# openSX70-dongle_v6-1-dual-led.net
KiCad netlist of a schematic drawn in EAGLE
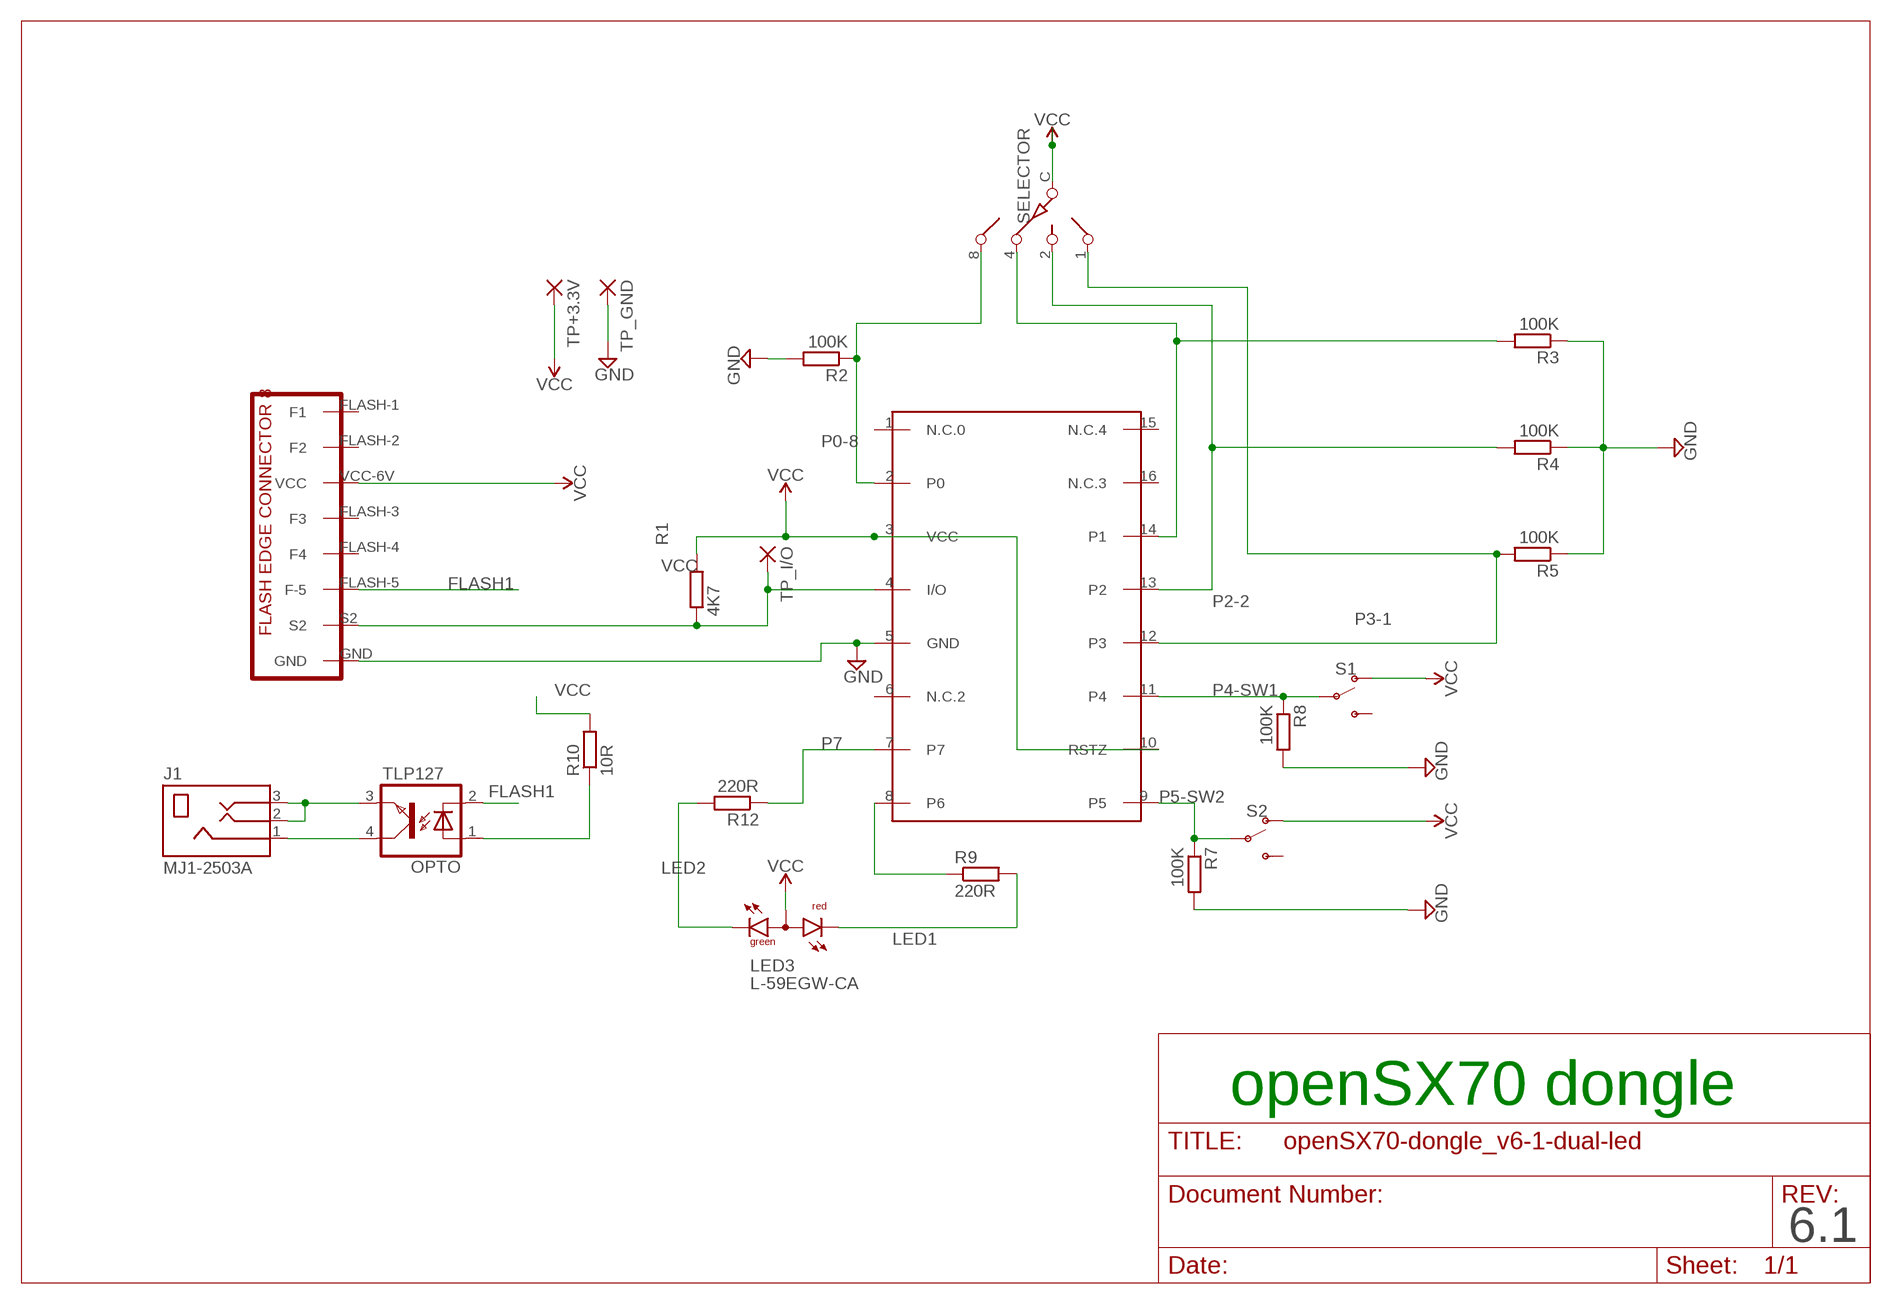
[diagram p0: schematic, sheet 1]

(export (version "E")
  (design (tool "Eeschema 10.0.6"))
  (components
    (comp (ref "DS2408")
      (value "DS2408")
      (footprint "eagle-import:SO16")
      (libsource (lib "eagle-import") (part "DS2408"))
    )
    (comp (ref "J1")
      (value "MJ1-2503A")
      (footprint "eagle-import:CUI_MJ1-2503A")
      (fields (field (name "DIGI-KEY_PART_NUMBER") "CP1-2503AM-ND") (field (name "MF") "CUI Inc."))
      (libsource (lib "eagle-import") (part "MJ1-2503A"))
    )
    (comp (ref "LED3")
      (value "L-59EGW-CA")
      (footprint "eagle-import:L-59EGW-CA")
      (libsource (lib "eagle-import") (part "L-59EGW-CA"))
    )
    (comp (ref "OPTO")
      (value "TLP127")
      (footprint "eagle-import:SO-4")
      (libsource (lib "eagle-import") (part "TLP127"))
    )
    (comp (ref "R1")
      (value "4K7")
      (footprint "eagle-import:R0603")
      (libsource (lib "eagle-import") (part "R-EU_R0603"))
    )
    (comp (ref "R2")
      (value "100K")
      (footprint "eagle-import:R0603")
      (libsource (lib "eagle-import") (part "R-EU_R0603"))
    )
    (comp (ref "R3")
      (value "100K")
      (footprint "eagle-import:R0603")
      (libsource (lib "eagle-import") (part "R-EU_R0603"))
    )
    (comp (ref "R4")
      (value "100K")
      (footprint "eagle-import:R0603")
      (libsource (lib "eagle-import") (part "R-EU_R0603"))
    )
    (comp (ref "R5")
      (value "100K")
      (footprint "eagle-import:R0603")
      (libsource (lib "eagle-import") (part "R-EU_R0603"))
    )
    (comp (ref "R7")
      (value "100K")
      (footprint "eagle-import:R0603")
      (libsource (lib "eagle-import") (part "R-EU_R0603"))
    )
    (comp (ref "R8")
      (value "100K")
      (footprint "eagle-import:R0603")
      (libsource (lib "eagle-import") (part "R-EU_R0603"))
    )
    (comp (ref "R9")
      (value "220R")
      (footprint "eagle-import:R0603")
      (libsource (lib "eagle-import") (part "R-EU_R0603"))
    )
    (comp (ref "R10")
      (value "10R")
      (footprint "eagle-import:R0603")
      (libsource (lib "eagle-import") (part "resistor_348_R-EU_R0603"))
    )
    (comp (ref "R12")
      (value "220R")
      (footprint "eagle-import:R0603")
      (libsource (lib "eagle-import") (part "R-EU_R0603"))
    )
    (comp (ref "S1")
      (value "SWITCH-SPDT-SMD-RIGHT-ANGLE")
      (footprint "eagle-import:SWITCH_SPST_SMD_A")
      (libsource (lib "eagle-import") (part "SWITCH-SPDT-SMD-RIGHT-ANGLE"))
    )
    (comp (ref "S2")
      (value "SWITCH-SPDT-SMD-RIGHT-ANGLE")
      (footprint "eagle-import:SWITCH_SPST_SMD_A")
      (libsource (lib "eagle-import") (part "SWITCH-SPDT-SMD-RIGHT-ANGLE"))
    )
    (comp (ref "SELECTOR")
      (value "SW-C16")
      (footprint "eagle-import:SW-C16")
      (libsource (lib "eagle-import") (part "SW-C16"))
    )
    (comp (ref "TP+3.3V")
      (value "SMD2")
      (footprint "eagle-import:SMD1,27-2,54")
      (libsource (lib "eagle-import") (part "SMD2"))
    )
    (comp (ref "TP_GND")
      (value "SMD2")
      (footprint "eagle-import:SMD1,27-2,54")
      (libsource (lib "eagle-import") (part "SMD2"))
    )
    (comp (ref "TP_I/O")
      (value "SMD2")
      (footprint "eagle-import:SMD1,27-2,54")
      (libsource (lib "eagle-import") (part "SMD2"))
    )
    (comp (ref "U$2")
      (value "SX70-FLASH-EDGE8-MALE-PROPER")
      (footprint "eagle-import:SX70-FLASH-EDGE8")
      (libsource (lib "eagle-import") (part "SX70-FLASH-EDGE8-MALE-PROPER"))
    )
  )
  (nets
    (net (code "1") (name "/FLASH1") (class "Default")
      (node (ref "OPTO") (pin "2") (pinfunction "C_2") (pintype "passive"))
      (node (ref "U$2") (pin "FLASH-5") (pinfunction "F-5_FLASH-5") (pintype "bidirectional"))
    )
    (net (code "2") (name "/LED1") (class "Default")
      (node (ref "LED3") (pin "1") (pinfunction "CR_1") (pintype "passive"))
      (node (ref "R9") (pin "2") (pinfunction "2_2") (pintype "passive"))
    )
    (net (code "3") (name "/LED2") (class "Default")
      (node (ref "LED3") (pin "3") (pinfunction "CG_3") (pintype "passive"))
      (node (ref "R12") (pin "2") (pinfunction "2_2") (pintype "passive"))
    )
    (net (code "4") (name "/P0-8") (class "Default")
      (node (ref "DS2408") (pin "2") (pinfunction "P0_2") (pintype "bidirectional"))
      (node (ref "R2") (pin "1") (pinfunction "1_1") (pintype "passive"))
      (node (ref "SELECTOR") (pin "8") (pinfunction "8_8") (pintype "passive"))
    )
    (net (code "5") (name "/P2-2") (class "Default")
      (node (ref "DS2408") (pin "13") (pinfunction "P2_13") (pintype "bidirectional"))
      (node (ref "R4") (pin "2") (pinfunction "2_2") (pintype "passive"))
      (node (ref "SELECTOR") (pin "2") (pinfunction "2_2") (pintype "passive"))
    )
    (net (code "6") (name "/P3-1") (class "Default")
      (node (ref "DS2408") (pin "12") (pinfunction "P3_12") (pintype "bidirectional"))
      (node (ref "R5") (pin "2") (pinfunction "2_2") (pintype "passive"))
      (node (ref "SELECTOR") (pin "1") (pinfunction "1_1") (pintype "passive"))
    )
    (net (code "7") (name "/P4-SW1") (class "Default")
      (node (ref "DS2408") (pin "11") (pinfunction "P4_11") (pintype "bidirectional"))
      (node (ref "R8") (pin "1") (pinfunction "1_1") (pintype "passive"))
      (node (ref "S1") (pin "2") (pinfunction "P_2") (pintype "passive"))
    )
    (net (code "8") (name "/P5-SW2") (class "Default")
      (node (ref "DS2408") (pin "9") (pinfunction "P5_9") (pintype "bidirectional"))
      (node (ref "R7") (pin "1") (pinfunction "1_1") (pintype "passive"))
      (node (ref "S2") (pin "2") (pinfunction "P_2") (pintype "passive"))
    )
    (net (code "9") (name "/P7") (class "Default")
      (node (ref "DS2408") (pin "7") (pinfunction "P7_7") (pintype "bidirectional"))
      (node (ref "R12") (pin "1") (pinfunction "1_1") (pintype "passive"))
    )
    (net (code "10") (name "GND") (class "Default")
      (node (ref "DS2408") (pin "5") (pinfunction "GND_5") (pintype "bidirectional"))
      (node (ref "R2") (pin "2") (pinfunction "2_2") (pintype "passive"))
      (node (ref "R3") (pin "1") (pinfunction "1_1") (pintype "passive"))
      (node (ref "R4") (pin "1") (pinfunction "1_1") (pintype "passive"))
      (node (ref "R5") (pin "1") (pinfunction "1_1") (pintype "passive"))
      (node (ref "R7") (pin "2") (pinfunction "2_2") (pintype "passive"))
      (node (ref "R8") (pin "2") (pinfunction "2_2") (pintype "passive"))
      (node (ref "TP_GND") (pin "1") (pinfunction "P_1") (pintype "passive"))
      (node (ref "U$2") (pin "GND") (pinfunction "GND_GND") (pintype "bidirectional"))
    )
    (net (code "11") (name "Net-(DS2408-I{slash}O)") (class "Default")
      (node (ref "DS2408") (pin "4") (pinfunction "I/O_4") (pintype "bidirectional"))
      (node (ref "R1") (pin "1") (pinfunction "1_1") (pintype "passive"))
      (node (ref "TP_I/O") (pin "1") (pinfunction "P_1") (pintype "passive"))
      (node (ref "U$2") (pin "S2") (pinfunction "S2_S2") (pintype "bidirectional"))
    )
    (net (code "12") (name "Net-(DS2408-P1)") (class "Default")
      (node (ref "DS2408") (pin "14") (pinfunction "P1_14") (pintype "bidirectional"))
      (node (ref "R3") (pin "2") (pinfunction "2_2") (pintype "passive"))
      (node (ref "SELECTOR") (pin "4") (pinfunction "4_4") (pintype "passive"))
    )
    (net (code "13") (name "Net-(DS2408-P6)") (class "Default")
      (node (ref "DS2408") (pin "8") (pinfunction "P6_8") (pintype "bidirectional"))
      (node (ref "R9") (pin "1") (pinfunction "1_1") (pintype "passive"))
    )
    (net (code "14") (name "Net-(OPTO-A)") (class "Default")
      (node (ref "OPTO") (pin "1") (pinfunction "A_1") (pintype "passive"))
      (node (ref "R10") (pin "1") (pinfunction "1_1") (pintype "passive"))
    )
    (net (code "15") (name "Net-(OPTO-COL)") (class "Default")
      (node (ref "J1") (pin "1") (pinfunction "1_1") (pintype "passive"))
      (node (ref "OPTO") (pin "4") (pinfunction "COL_4") (pintype "passive"))
    )
    (net (code "16") (name "Net-(OPTO-EMIT)") (class "Default")
      (node (ref "J1") (pin "2") (pinfunction "2_2") (pintype "passive"))
      (node (ref "J1") (pin "3") (pinfunction "3_3") (pintype "passive"))
      (node (ref "OPTO") (pin "3") (pinfunction "EMIT_3") (pintype "passive"))
    )
    (net (code "17") (name "VCC") (class "Default")
      (node (ref "DS2408") (pin "10") (pinfunction "RSTZ_10") (pintype "bidirectional"))
      (node (ref "DS2408") (pin "3") (pinfunction "VCC_3") (pintype "bidirectional"))
      (node (ref "LED3") (pin "2") (pinfunction "A_2") (pintype "passive"))
      (node (ref "R1") (pin "2") (pinfunction "2_2") (pintype "passive"))
      (node (ref "R10") (pin "2") (pinfunction "2_2") (pintype "passive"))
      (node (ref "S1") (pin "1") (pinfunction "O_1") (pintype "passive"))
      (node (ref "S2") (pin "1") (pinfunction "O_1") (pintype "passive"))
      (node (ref "SELECTOR") (pin "C") (pinfunction "C_C") (pintype "passive"))
      (node (ref "TP+3.3V") (pin "1") (pinfunction "P_1") (pintype "passive"))
      (node (ref "U$2") (pin "VCC-6V") (pinfunction "VCC_VCC-6V") (pintype "bidirectional"))
    )
    (net (code "18") (name "unconnected-(DS2408-N.C.0-Pad1)") (class "Default")
      (node (ref "DS2408") (pin "1") (pinfunction "N.C.0_1") (pintype "bidirectional"))
    )
    (net (code "19") (name "unconnected-(DS2408-N.C.2-Pad6)") (class "Default")
      (node (ref "DS2408") (pin "6") (pinfunction "N.C.2_6") (pintype "bidirectional"))
    )
    (net (code "20") (name "unconnected-(DS2408-N.C.3-Pad16)") (class "Default")
      (node (ref "DS2408") (pin "16") (pinfunction "N.C.3_16") (pintype "bidirectional"))
    )
    (net (code "21") (name "unconnected-(DS2408-N.C.4-Pad15)") (class "Default")
      (node (ref "DS2408") (pin "15") (pinfunction "N.C.4_15") (pintype "bidirectional"))
    )
    (net (code "22") (name "unconnected-(S1-S-Pad3)") (class "Default")
      (node (ref "S1") (pin "3") (pinfunction "S_3") (pintype "passive"))
    )
    (net (code "23") (name "unconnected-(S2-S-Pad3)") (class "Default")
      (node (ref "S2") (pin "3") (pinfunction "S_3") (pintype "passive"))
    )
    (net (code "24") (name "unconnected-(U$2-F1-PadFLASH-1)") (class "Default")
      (node (ref "U$2") (pin "FLASH-1") (pinfunction "F1_FLASH-1") (pintype "bidirectional"))
    )
    (net (code "25") (name "unconnected-(U$2-F2-PadFLASH-2)") (class "Default")
      (node (ref "U$2") (pin "FLASH-2") (pinfunction "F2_FLASH-2") (pintype "bidirectional"))
    )
    (net (code "26") (name "unconnected-(U$2-F3-PadFLASH-3)") (class "Default")
      (node (ref "U$2") (pin "FLASH-3") (pinfunction "F3_FLASH-3") (pintype "bidirectional"))
    )
    (net (code "27") (name "unconnected-(U$2-F4-PadFLASH-4)") (class "Default")
      (node (ref "U$2") (pin "FLASH-4") (pinfunction "F4_FLASH-4") (pintype "bidirectional"))
    )
  )
)
